# Artemis_Thing_Plus.net
KiCad netlist of a schematic drawn in EAGLE
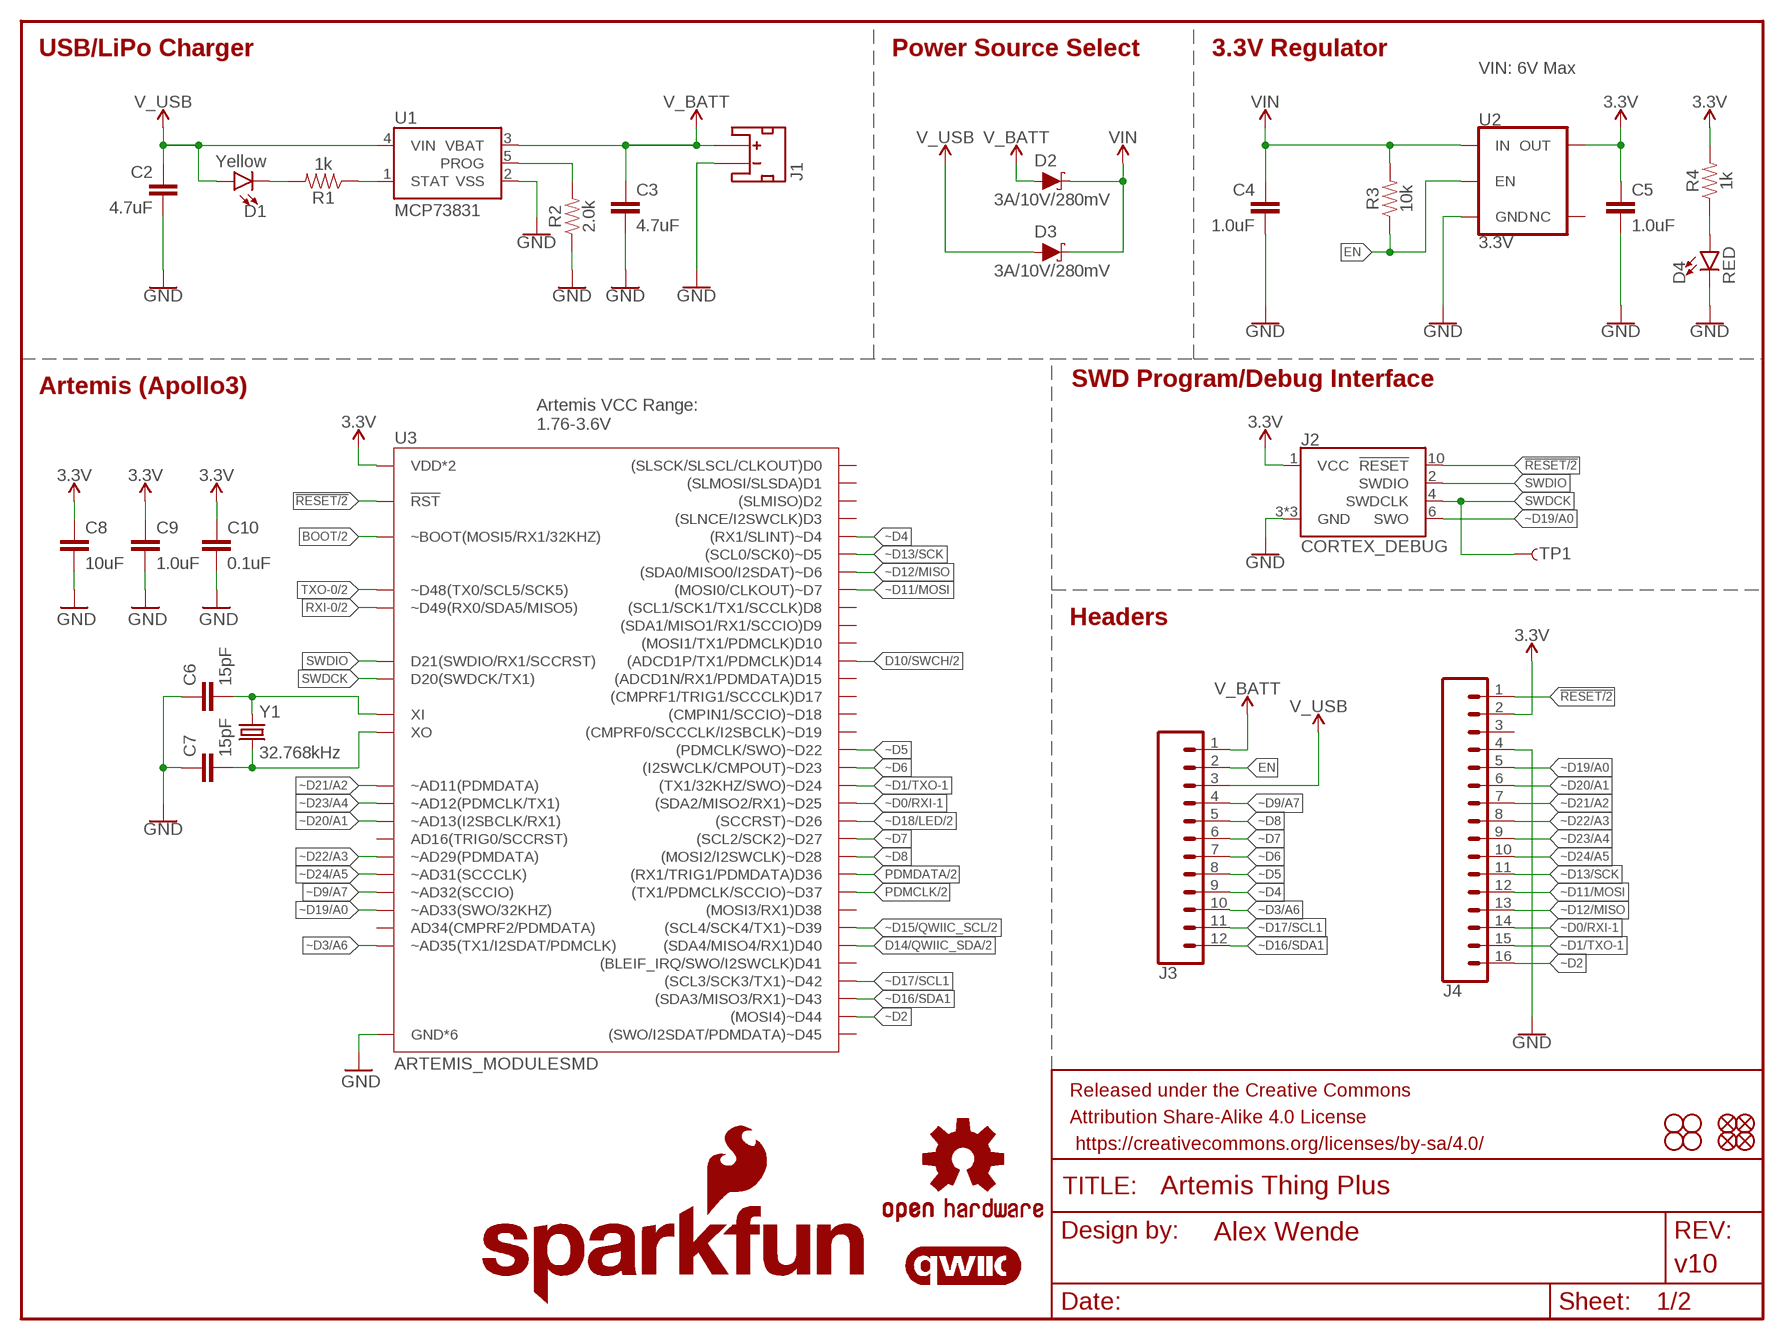
[diagram p0: schematic, sheet 1]
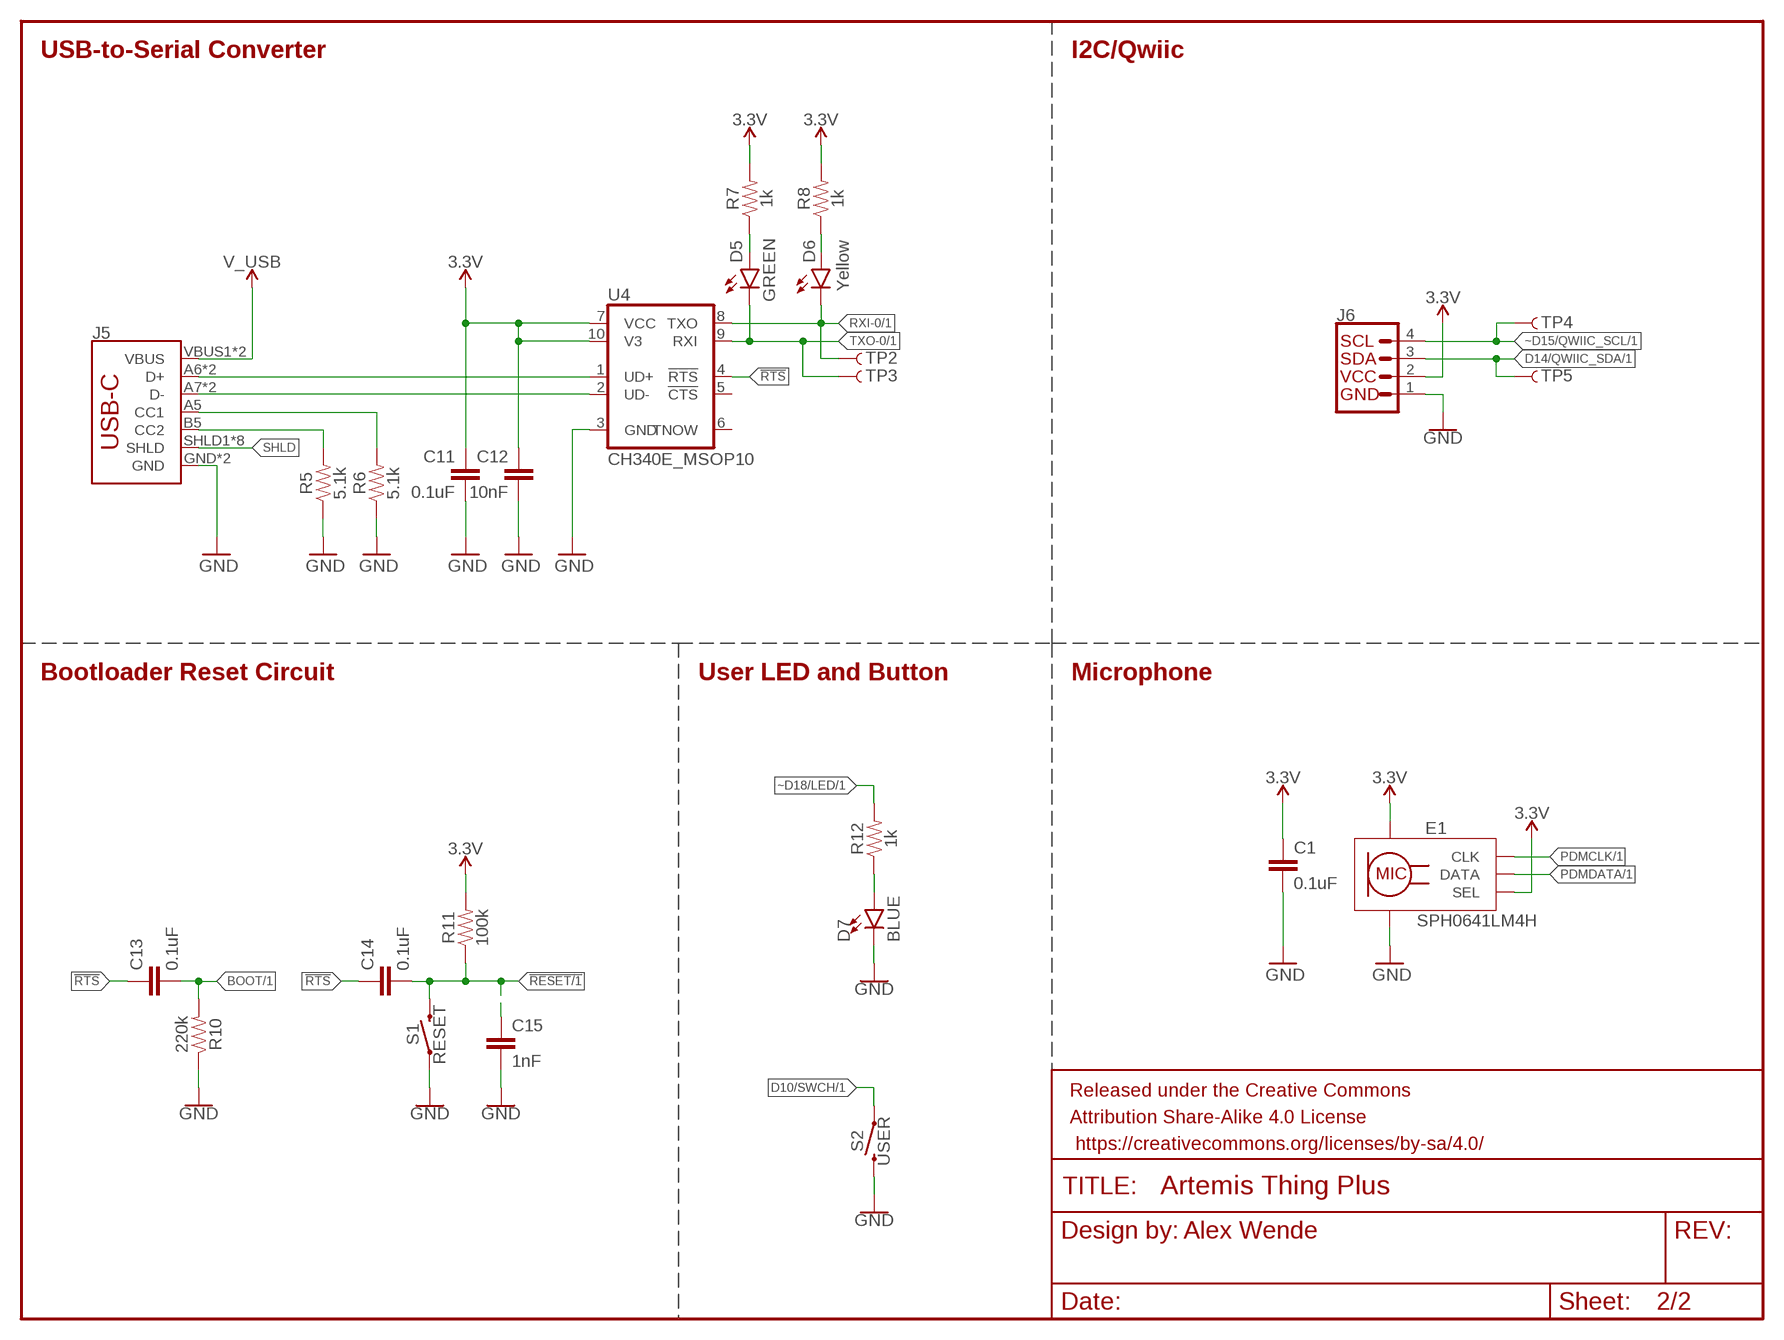
[diagram p1: schematic, sheet 2]

(export (version "E")
  (design (tool "Eeschema 10.0.6"))
  (components
    (comp (ref "C2")
      (value "4.7uF")
      (footprint "eagle-import:0603")
      (libsource (lib "eagle-import") (part "4.7UF-0603-6.3V-(10%)"))
    )
    (comp (ref "C3")
      (value "4.7uF")
      (footprint "eagle-import:0603")
      (libsource (lib "eagle-import") (part "4.7UF-0603-6.3V-(10%)"))
    )
    (comp (ref "C4")
      (value "1.0uF")
      (footprint "eagle-import:0402-TIGHT")
      (libsource (lib "eagle-import") (part "1.0UF-0402T-16V-10%"))
    )
    (comp (ref "C5")
      (value "1.0uF")
      (footprint "eagle-import:0402-TIGHT")
      (libsource (lib "eagle-import") (part "1.0UF-0402T-16V-10%"))
    )
    (comp (ref "C6")
      (value "15pF")
      (footprint "eagle-import:0603")
      (libsource (lib "eagle-import") (part "15PF-0603-50V-5%"))
    )
    (comp (ref "C7")
      (value "15pF")
      (footprint "eagle-import:0603")
      (libsource (lib "eagle-import") (part "15PF-0603-50V-5%"))
    )
    (comp (ref "C8")
      (value "10uF")
      (footprint "eagle-import:0603")
      (libsource (lib "eagle-import") (part "10UF-0603-6.3V-20%"))
    )
    (comp (ref "C9")
      (value "1.0uF")
      (footprint "eagle-import:0603")
      (libsource (lib "eagle-import") (part "1.0UF-0603-16V-10%"))
    )
    (comp (ref "C10")
      (value "0.1uF")
      (footprint "eagle-import:0603")
      (libsource (lib "eagle-import") (part "0.1UF-0603-25V-(+80/-20%)"))
    )
    (comp (ref "D1")
      (value "Yellow")
      (footprint "eagle-import:LED-0603")
      (libsource (lib "eagle-import") (part "LED-YELLOW0603"))
    )
    (comp (ref "D2")
      (value "3A/10V/280mV")
      (footprint "eagle-import:SOD-323")
      (libsource (lib "eagle-import") (part "DIODE-SCHOTTKY-BAT60A"))
    )
    (comp (ref "D3")
      (value "3A/10V/280mV")
      (footprint "eagle-import:SOD-323")
      (libsource (lib "eagle-import") (part "DIODE-SCHOTTKY-BAT60A"))
    )
    (comp (ref "D4")
      (value "RED")
      (footprint "eagle-import:LED-0603")
      (libsource (lib "eagle-import") (part "LED-RED0603"))
    )
    (comp (ref "FD1")
      (value "FIDUCIALUFIDUCIAL")
      (footprint "eagle-import:FIDUCIAL-MICRO")
      (libsource (lib "eagle-import") (part "FIDUCIALUFIDUCIAL"))
    )
    (comp (ref "FD2")
      (value "FIDUCIALUFIDUCIAL")
      (footprint "eagle-import:FIDUCIAL-MICRO")
      (libsource (lib "eagle-import") (part "FIDUCIALUFIDUCIAL"))
    )
    (comp (ref "FD3")
      (value "FIDUCIALUFIDUCIAL")
      (footprint "eagle-import:FIDUCIAL-MICRO")
      (libsource (lib "eagle-import") (part "FIDUCIALUFIDUCIAL"))
    )
    (comp (ref "FD4")
      (value "FIDUCIALUFIDUCIAL")
      (footprint "eagle-import:FIDUCIAL-MICRO")
      (libsource (lib "eagle-import") (part "FIDUCIALUFIDUCIAL"))
    )
    (comp (ref "FRAME1")
      (value "FRAME-LETTER")
      (footprint "eagle-import:CREATIVE_COMMONS")
      (fields (field (name "DESIGNER") "Alex Wende") (field (name "REV") "v10"))
      (libsource (lib "eagle-import") (part "FRAME-LETTER"))
    )
    (comp (ref "H1")
      (value "STAND-OFF")
      (footprint "eagle-import:STAND-OFF")
      (libsource (lib "eagle-import") (part "STAND-OFF"))
    )
    (comp (ref "H2")
      (value "STAND-OFF")
      (footprint "eagle-import:STAND-OFF")
      (libsource (lib "eagle-import") (part "STAND-OFF"))
    )
    (comp (ref "H3")
      (value "STAND-OFF")
      (footprint "eagle-import:STAND-OFF")
      (libsource (lib "eagle-import") (part "STAND-OFF"))
    )
    (comp (ref "H4")
      (value "STAND-OFF")
      (footprint "eagle-import:STAND-OFF")
      (libsource (lib "eagle-import") (part "STAND-OFF"))
    )
    (comp (ref "J1")
      (value "JST_2MM_MALE")
      (footprint "eagle-import:JST-2-SMD")
      (libsource (lib "eagle-import") (part "JST_2MM_MALE"))
    )
    (comp (ref "J2")
      (value "CORTEX_DEBUG")
      (footprint "eagle-import:2X5-PTH-1.27MM-NO_SILK")
      (libsource (lib "eagle-import") (part "CORTEX_DEBUG_MINIMUM_PTH_NS"))
    )
    (comp (ref "J3")
      (value "CONN_12SM_SQ_NO_SILK")
      (footprint "eagle-import:1X12_SM_SQ_NOSILK")
      (libsource (lib "eagle-import") (part "CONN_12SM_SQ_NO_SILK"))
    )
    (comp (ref "J4")
      (value "CONN_161X16_SM_SQ_NOSILK")
      (footprint "eagle-import:1X16_SM_SQ_NOSILK")
      (libsource (lib "eagle-import") (part "CONN_161X16_SM_SQ_NOSILK"))
    )
    (comp (ref "LOGO1")
      (value "OSHW-LOGOS")
      (footprint "eagle-import:OSHW-LOGO-S")
      (libsource (lib "eagle-import") (part "OSHW-LOGOS"))
    )
    (comp (ref "LOGO2")
      (value "QWIIC_LOGO_5MM")
      (footprint "eagle-import:QWIIC_5MM")
      (libsource (lib "eagle-import") (part "QWIIC_LOGO_5MM"))
    )
    (comp (ref "LOGO3")
      (value "SFE_LOGO_NAME_FLAME.1_INCH")
      (footprint "eagle-import:SFE_LOGO_NAME_FLAME_.1")
      (libsource (lib "eagle-import") (part "SFE_LOGO_NAME_FLAME.1_INCH"))
    )
    (comp (ref "R1")
      (value "1k")
      (footprint "eagle-import:0603")
      (libsource (lib "eagle-import") (part "1KOHM-0603-1/10W-1%"))
    )
    (comp (ref "R2")
      (value "2.0k")
      (footprint "eagle-import:0603")
      (libsource (lib "eagle-import") (part "2.0KOHM-0603-1/10W-5%"))
    )
    (comp (ref "R3")
      (value "10k")
      (footprint "eagle-import:0603")
      (libsource (lib "eagle-import") (part "10KOHM-0603-1/10W-1%"))
    )
    (comp (ref "R4")
      (value "1k")
      (footprint "eagle-import:0603")
      (libsource (lib "eagle-import") (part "1KOHM-0603-1/10W-1%"))
    )
    (comp (ref "TP1")
      (value "TEST-POINTTP_15TH_THRU")
      (footprint "eagle-import:TP_15TH")
      (libsource (lib "eagle-import") (part "TEST-POINTTP_15TH_THRU"))
    )
    (comp (ref "U1")
      (value "MCP73831")
      (footprint "eagle-import:SOT23-5")
      (libsource (lib "eagle-import") (part "MCP73831"))
    )
    (comp (ref "U2")
      (value "3.3V")
      (footprint "eagle-import:SOT23-5")
      (libsource (lib "eagle-import") (part "V_REG_AP2112K-3.3V"))
    )
    (comp (ref "U3")
      (value "ARTEMIS_MODULESMD")
      (footprint "eagle-import:ARTEMIS_FP")
      (libsource (lib "eagle-import") (part "ARTEMIS_MODULESMD"))
    )
    (comp (ref "Y1")
      (value "32.768kHz")
      (footprint "eagle-import:CRYSTAL-SMD-3.2X1.5MM")
      (libsource (lib "eagle-import") (part "CRYSTAL-32.768KHZSMD-3.2X1.5"))
    )
    (comp (ref "C1")
      (value "0.1uF")
      (footprint "eagle-import:0402-TIGHT")
      (libsource (lib "eagle-import") (part "0.1UF-0402T-16V-10%"))
    )
    (comp (ref "C11")
      (value "0.1uF")
      (footprint "eagle-import:0603")
      (libsource (lib "eagle-import") (part "0.1UF-0603-25V-(+80/-20%)"))
    )
    (comp (ref "C12")
      (value "10nF")
      (footprint "eagle-import:0603")
      (libsource (lib "eagle-import") (part "10NF-0603-50V-10%"))
    )
    (comp (ref "C13")
      (value "0.1uF")
      (footprint "eagle-import:0603")
      (libsource (lib "eagle-import") (part "0.1UF-0603-25V-5%"))
    )
    (comp (ref "C14")
      (value "0.1uF")
      (footprint "eagle-import:0603")
      (libsource (lib "eagle-import") (part "0.1UF-0603-25V-5%"))
    )
    (comp (ref "C15")
      (value "1nF")
      (footprint "eagle-import:0603")
      (libsource (lib "eagle-import") (part "1.0NF/1000PF-0603-50V-10%"))
    )
    (comp (ref "D5")
      (value "GREEN")
      (footprint "eagle-import:LED-0603")
      (libsource (lib "eagle-import") (part "LED-GREEN0603"))
    )
    (comp (ref "D6")
      (value "Yellow")
      (footprint "eagle-import:LED-0603")
      (libsource (lib "eagle-import") (part "LED-YELLOW0603"))
    )
    (comp (ref "D7")
      (value "BLUE")
      (footprint "eagle-import:LED-0603")
      (libsource (lib "eagle-import") (part "LED-BLUE0603"))
    )
    (comp (ref "E1")
      (value "SPH0641LM4H")
      (footprint "eagle-import:SPH0641LM4H-1_MICROPHONE")
      (libsource (lib "eagle-import") (part "SPH0641LM4H-1_MICROPHONE"))
    )
    (comp (ref "FRAME2")
      (value "FRAME-LETTERNO_PACKAGE")
      (footprint "eagle-import:DUMMY")
      (fields (field (name "DESIGNER") "Nobody"))
      (libsource (lib "eagle-import") (part "FRAME-LETTERNO_PACKAGE"))
    )
    (comp (ref "J5")
      (value "USB-C")
      (footprint "eagle-import:USB-C-16P")
      (libsource (lib "eagle-import") (part "USB_C2-LAYER"))
    )
    (comp (ref "J6")
      (value "QWIIC_CONNECTORJS-1MM")
      (footprint "eagle-import:JST04_1MM_RA")
      (libsource (lib "eagle-import") (part "QWIIC_CONNECTORJS-1MM"))
    )
    (comp (ref "R5")
      (value "5.1k")
      (footprint "eagle-import:0603")
      (libsource (lib "eagle-import") (part "5.1KOHM5.1KOHM-0603-1/10W-1%"))
    )
    (comp (ref "R6")
      (value "5.1k")
      (footprint "eagle-import:0603")
      (libsource (lib "eagle-import") (part "5.1KOHM5.1KOHM-0603-1/10W-1%"))
    )
    (comp (ref "R7")
      (value "1k")
      (footprint "eagle-import:0603")
      (libsource (lib "eagle-import") (part "1KOHM-0603-1/10W-1%"))
    )
    (comp (ref "R8")
      (value "1k")
      (footprint "eagle-import:0603")
      (libsource (lib "eagle-import") (part "1KOHM-0603-1/10W-1%"))
    )
    (comp (ref "R10")
      (value "220k")
      (footprint "eagle-import:0603")
      (libsource (lib "eagle-import") (part "220KOHM-0603-1/10W-1%"))
    )
    (comp (ref "R11")
      (value "100k")
      (footprint "eagle-import:0603")
      (libsource (lib "eagle-import") (part "100KOHM-0603-1/10W-1%"))
    )
    (comp (ref "R12")
      (value "1k")
      (footprint "eagle-import:0603")
      (libsource (lib "eagle-import") (part "1KOHM-0603-1/10W-1%"))
    )
    (comp (ref "S1")
      (value "RESET")
      (footprint "eagle-import:TACTILE_SWITCH_SMD_4.6X2.8MM")
      (libsource (lib "eagle-import") (part "MOMENTARY-SWITCH-SPST-SMD-4.6X2.8MM"))
    )
    (comp (ref "S2")
      (value "USER")
      (footprint "eagle-import:TACTILE_SWITCH_SMD_4.6X2.8MM")
      (libsource (lib "eagle-import") (part "MOMENTARY-SWITCH-SPST-SMD-4.6X2.8MM"))
    )
    (comp (ref "TP2")
      (value "TEST-POINTTP_15TH_THRU")
      (footprint "eagle-import:TP_15TH")
      (libsource (lib "eagle-import") (part "TEST-POINTTP_15TH_THRU"))
    )
    (comp (ref "TP3")
      (value "TEST-POINTTP_15TH_THRU")
      (footprint "eagle-import:TP_15TH")
      (libsource (lib "eagle-import") (part "TEST-POINTTP_15TH_THRU"))
    )
    (comp (ref "TP4")
      (value "TEST-POINTTP_15TH_THRU")
      (footprint "eagle-import:TP_15TH")
      (libsource (lib "eagle-import") (part "TEST-POINTTP_15TH_THRU"))
    )
    (comp (ref "TP5")
      (value "TEST-POINTTP_15TH_THRU")
      (footprint "eagle-import:TP_15TH")
      (libsource (lib "eagle-import") (part "TEST-POINTTP_15TH_THRU"))
    )
    (comp (ref "U4")
      (value "CH340E_MSOP10")
      (footprint "eagle-import:MSOP10")
      (libsource (lib "eagle-import") (part "CH340E_MSOP10"))
    )
  )
  (nets
    (net (code "1") (name "3.3V") (class "Default")
      (node (ref "C1") (pin "1") (pinfunction "1_1") (pintype "passive"))
      (node (ref "C10") (pin "1") (pinfunction "1_1") (pintype "passive"))
      (node (ref "C11") (pin "1") (pinfunction "1_1") (pintype "passive"))
      (node (ref "C12") (pin "1") (pinfunction "1_1") (pintype "passive"))
      (node (ref "C5") (pin "1") (pinfunction "1_1") (pintype "passive"))
      (node (ref "C8") (pin "1") (pinfunction "1_1") (pintype "passive"))
      (node (ref "C9") (pin "1") (pinfunction "1_1") (pintype "passive"))
      (node (ref "E1") (pin "2") (pinfunction "SEL_2") (pintype "input"))
      (node (ref "E1") (pin "5") (pinfunction "VDD_5") (pintype "power_in"))
      (node (ref "J2") (pin "1") (pinfunction "VCC_1") (pintype "bidirectional"))
      (node (ref "J4") (pin "2") (pinfunction "2_2") (pintype "passive"))
      (node (ref "J6") (pin "2") (pinfunction "2_2") (pintype "power_in"))
      (node (ref "R11") (pin "2") (pinfunction "2_2") (pintype "passive"))
      (node (ref "R4") (pin "2") (pinfunction "2_2") (pintype "passive"))
      (node (ref "R7") (pin "2") (pinfunction "2_2") (pintype "passive"))
      (node (ref "R8") (pin "2") (pinfunction "2_2") (pintype "passive"))
      (node (ref "U2") (pin "5") (pinfunction "OUT_5") (pintype "passive"))
      (node (ref "U3") (pin "VDD@36") (pinfunction "VDD*2_VDD@36") (pintype "bidirectional"))
      (node (ref "U3") (pin "VDD@37") (pinfunction "VDD*2_VDD@37") (pintype "bidirectional"))
      (node (ref "U4") (pin "10") (pinfunction "V3_10") (pintype "bidirectional"))
      (node (ref "U4") (pin "7") (pinfunction "VCC_7") (pintype "bidirectional"))
    )
    (net (code "2") (name "BOOT") (class "Default")
      (node (ref "C13") (pin "2") (pinfunction "2_2") (pintype "passive"))
      (node (ref "R10") (pin "2") (pinfunction "2_2") (pintype "passive"))
      (node (ref "U3") (pin "BOOT") (pinfunction "~{BOOT(MOSI5/RX1/32KHZ})_BOOT") (pintype "bidirectional"))
    )
    (net (code "3") (name "D10{slash}SWCH") (class "Default")
      (node (ref "S2") (pin "1") (pinfunction "1_1") (pintype "passive"))
      (node (ref "S2") (pin "2") (pinfunction "1_2") (pintype "passive"))
      (node (ref "U3") (pin "D14") (pinfunction "(ADCD1P/TX1/PDMCLK)D14_D14") (pintype "bidirectional"))
    )
    (net (code "4") (name "D14{slash}QWIIC_SDA") (class "Default")
      (node (ref "J6") (pin "3") (pinfunction "3_3") (pintype "passive"))
      (node (ref "TP5") (pin "P$1") (pinfunction "1_P$1") (pintype "bidirectional"))
      (node (ref "U3") (pin "D40") (pinfunction "(SDA4/MISO4/RX1)D40_D40") (pintype "bidirectional"))
    )
    (net (code "5") (name "EN") (class "Default")
      (node (ref "J3") (pin "2") (pinfunction "2_2") (pintype "passive"))
      (node (ref "R3") (pin "1") (pinfunction "1_1") (pintype "passive"))
      (node (ref "U2") (pin "3") (pinfunction "EN_3") (pintype "input"))
    )
    (net (code "6") (name "GND") (class "Default")
      (node (ref "C1") (pin "2") (pinfunction "2_2") (pintype "passive"))
      (node (ref "C10") (pin "2") (pinfunction "2_2") (pintype "passive"))
      (node (ref "C11") (pin "2") (pinfunction "2_2") (pintype "passive"))
      (node (ref "C12") (pin "2") (pinfunction "2_2") (pintype "passive"))
      (node (ref "C15") (pin "2") (pinfunction "2_2") (pintype "passive"))
      (node (ref "C2") (pin "2") (pinfunction "2_2") (pintype "passive"))
      (node (ref "C3") (pin "2") (pinfunction "2_2") (pintype "passive"))
      (node (ref "C4") (pin "2") (pinfunction "2_2") (pintype "passive"))
      (node (ref "C5") (pin "2") (pinfunction "2_2") (pintype "passive"))
      (node (ref "C6") (pin "1") (pinfunction "1_1") (pintype "passive"))
      (node (ref "C7") (pin "1") (pinfunction "1_1") (pintype "passive"))
      (node (ref "C8") (pin "2") (pinfunction "2_2") (pintype "passive"))
      (node (ref "C9") (pin "2") (pinfunction "2_2") (pintype "passive"))
      (node (ref "D4") (pin "C") (pinfunction "C_C") (pintype "passive"))
      (node (ref "D7") (pin "C") (pinfunction "C_C") (pintype "passive"))
      (node (ref "E1") (pin "3") (pinfunction "GND_3") (pintype "power_in"))
      (node (ref "E1") (pin "6") (pinfunction "GND_6") (pintype "power_in"))
      (node (ref "E1") (pin "7") (pinfunction "GND_7") (pintype "power_in"))
      (node (ref "E1") (pin "8") (pinfunction "GND_8") (pintype "power_in"))
      (node (ref "J1") (pin "1") (pinfunction "-_1") (pintype "bidirectional"))
      (node (ref "J2") (pin "3") (pinfunction "GND_3") (pintype "bidirectional"))
      (node (ref "J2") (pin "5") (pinfunction "GND_5") (pintype "bidirectional"))
      (node (ref "J2") (pin "9") (pinfunction "GND_9") (pintype "bidirectional"))
      (node (ref "J4") (pin "4") (pinfunction "4_4") (pintype "passive"))
      (node (ref "J5") (pin "GND") (pinfunction "GND_GND") (pintype "bidirectional"))
      (node (ref "J5") (pin "GND2") (pinfunction "GND_GND2") (pintype "bidirectional"))
      (node (ref "J6") (pin "1") (pinfunction "1_1") (pintype "power_in"))
      (node (ref "R10") (pin "1") (pinfunction "1_1") (pintype "passive"))
      (node (ref "R2") (pin "1") (pinfunction "1_1") (pintype "passive"))
      (node (ref "R5") (pin "1") (pinfunction "1_1") (pintype "passive"))
      (node (ref "R6") (pin "1") (pinfunction "1_1") (pintype "passive"))
      (node (ref "S1") (pin "1") (pinfunction "1_1") (pintype "passive"))
      (node (ref "S1") (pin "2") (pinfunction "1_2") (pintype "passive"))
      (node (ref "S2") (pin "3") (pinfunction "2_3") (pintype "passive"))
      (node (ref "S2") (pin "4") (pinfunction "2_4") (pintype "passive"))
      (node (ref "U1") (pin "2") (pinfunction "VSS_2") (pintype "power_in"))
      (node (ref "U2") (pin "2") (pinfunction "GND_2") (pintype "input"))
      (node (ref "U3") (pin "GND@1") (pinfunction "GND*6_GND@1") (pintype "bidirectional"))
      (node (ref "U3") (pin "GND@22") (pinfunction "GND*6_GND@22") (pintype "bidirectional"))
      (node (ref "U3") (pin "GND@38") (pinfunction "GND*6_GND@38") (pintype "bidirectional"))
      (node (ref "U3") (pin "GND@39") (pinfunction "GND*6_GND@39") (pintype "bidirectional"))
      (node (ref "U3") (pin "GND@47") (pinfunction "GND*6_GND@47") (pintype "bidirectional"))
      (node (ref "U3") (pin "GND@59") (pinfunction "GND*6_GND@59") (pintype "bidirectional"))
      (node (ref "U4") (pin "3") (pinfunction "GND_3") (pintype "bidirectional"))
    )
    (net (code "7") (name "Net-(D1-PadC)") (class "Default")
      (node (ref "D1") (pin "C") (pinfunction "C_C") (pintype "passive"))
      (node (ref "R1") (pin "2") (pinfunction "2_2") (pintype "passive"))
    )
    (net (code "8") (name "Net-(D4-PadA)") (class "Default")
      (node (ref "D4") (pin "A") (pinfunction "A_A") (pintype "passive"))
      (node (ref "R4") (pin "1") (pinfunction "1_1") (pintype "passive"))
    )
    (net (code "9") (name "Net-(D5-PadA)") (class "Default")
      (node (ref "D5") (pin "A") (pinfunction "A_A") (pintype "passive"))
      (node (ref "R7") (pin "1") (pinfunction "1_1") (pintype "passive"))
    )
    (net (code "10") (name "Net-(D6-PadA)") (class "Default")
      (node (ref "D6") (pin "A") (pinfunction "A_A") (pintype "passive"))
      (node (ref "R8") (pin "1") (pinfunction "1_1") (pintype "passive"))
    )
    (net (code "11") (name "Net-(D7-PadA)") (class "Default")
      (node (ref "D7") (pin "A") (pinfunction "A_A") (pintype "passive"))
      (node (ref "R12") (pin "1") (pinfunction "1_1") (pintype "passive"))
    )
    (net (code "12") (name "Net-(J5-CC1)") (class "Default")
      (node (ref "J5") (pin "A5") (pinfunction "CC1_A5") (pintype "bidirectional"))
      (node (ref "R6") (pin "2") (pinfunction "2_2") (pintype "passive"))
    )
    (net (code "13") (name "Net-(J5-CC2)") (class "Default")
      (node (ref "J5") (pin "B5") (pinfunction "CC2_B5") (pintype "bidirectional"))
      (node (ref "R5") (pin "2") (pinfunction "2_2") (pintype "passive"))
    )
    (net (code "14") (name "Net-(U1-PROG)") (class "Default")
      (node (ref "R2") (pin "2") (pinfunction "2_2") (pintype "passive"))
      (node (ref "U1") (pin "5") (pinfunction "PROG_5") (pintype "input"))
    )
    (net (code "15") (name "Net-(U1-STAT)") (class "Default")
      (node (ref "R1") (pin "1") (pinfunction "1_1") (pintype "passive"))
      (node (ref "U1") (pin "1") (pinfunction "STAT_1") (pintype "output"))
    )
    (net (code "16") (name "Net-(U4-UD+)") (class "Default")
      (node (ref "J5") (pin "A6") (pinfunction "D+_A6") (pintype "bidirectional"))
      (node (ref "J5") (pin "B6") (pinfunction "D+_B6") (pintype "bidirectional"))
      (node (ref "U4") (pin "1") (pinfunction "UD+_1") (pintype "bidirectional"))
    )
    (net (code "17") (name "Net-(U4-UD-)") (class "Default")
      (node (ref "J5") (pin "A7") (pinfunction "D-_A7") (pintype "bidirectional"))
      (node (ref "J5") (pin "B7") (pinfunction "D-_B7") (pintype "bidirectional"))
      (node (ref "U4") (pin "2") (pinfunction "UD-_2") (pintype "bidirectional"))
    )
    (net (code "18") (name "Net-(Y1-1)") (class "Default")
      (node (ref "C6") (pin "2") (pinfunction "2_2") (pintype "passive"))
      (node (ref "U3") (pin "XI") (pinfunction "XI_XI") (pintype "bidirectional"))
      (node (ref "Y1") (pin "P$1") (pinfunction "1_P$1") (pintype "passive"))
    )
    (net (code "19") (name "Net-(Y1-2)") (class "Default")
      (node (ref "C7") (pin "2") (pinfunction "2_2") (pintype "passive"))
      (node (ref "U3") (pin "XO") (pinfunction "XO_XO") (pintype "bidirectional"))
      (node (ref "Y1") (pin "P$2") (pinfunction "2_P$2") (pintype "passive"))
    )
    (net (code "20") (name "PDMCLK") (class "Default")
      (node (ref "E1") (pin "4") (pinfunction "CLK_4") (pintype "input"))
      (node (ref "U3") (pin "~D37") (pinfunction "(TX1/PDMCLK/SCCIO)~{D37}_~D37") (pintype "bidirectional"))
    )
    (net (code "21") (name "PDMDATA") (class "Default")
      (node (ref "E1") (pin "1") (pinfunction "DATA_1") (pintype "output"))
      (node (ref "U3") (pin "D36") (pinfunction "(RX1/TRIG1/PDMDATA)D36_D36") (pintype "bidirectional"))
    )
    (net (code "22") (name "RXI-0") (class "Default")
      (node (ref "D6") (pin "C") (pinfunction "C_C") (pintype "passive"))
      (node (ref "TP2") (pin "P$1") (pinfunction "1_P$1") (pintype "bidirectional"))
      (node (ref "U3") (pin "RXI-0") (pinfunction "~{D49(RX0/SDA5/MISO5})_RXI-0") (pintype "bidirectional"))
      (node (ref "U4") (pin "8") (pinfunction "TXO_8") (pintype "bidirectional"))
    )
    (net (code "23") (name "SHLD") (class "Default")
      (node (ref "J5") (pin "SHLD1") (pinfunction "SHLD_SHLD1") (pintype "bidirectional"))
      (node (ref "J5") (pin "SHLD2") (pinfunction "SHLD_SHLD2") (pintype "bidirectional"))
      (node (ref "J5") (pin "SHLD3") (pinfunction "SHLD_SHLD3") (pintype "bidirectional"))
      (node (ref "J5") (pin "SHLD4") (pinfunction "SHLD_SHLD4") (pintype "bidirectional"))
      (node (ref "J5") (pin "SHLD5") (pinfunction "SHLD_SHLD5") (pintype "bidirectional"))
      (node (ref "J5") (pin "SHLD6") (pinfunction "SHLD_SHLD6") (pintype "bidirectional"))
      (node (ref "J5") (pin "SHLD7") (pinfunction "SHLD_SHLD7") (pintype "bidirectional"))
      (node (ref "J5") (pin "SHLD8") (pinfunction "SHLD_SHLD8") (pintype "bidirectional"))
    )
    (net (code "24") (name "SWDCK") (class "Default")
      (node (ref "J2") (pin "4") (pinfunction "SWDCLK_4") (pintype "bidirectional"))
      (node (ref "TP1") (pin "P$1") (pinfunction "1_P$1") (pintype "bidirectional"))
      (node (ref "U3") (pin "SWDCK") (pinfunction "D20(SWDCK/TX1)_SWDCK") (pintype "bidirectional"))
    )
    (net (code "25") (name "SWDIO") (class "Default")
      (node (ref "J2") (pin "2") (pinfunction "SWDIO_2") (pintype "bidirectional"))
      (node (ref "U3") (pin "SWDIO") (pinfunction "D21(SWDIO/RX1/SCCRST)_SWDIO") (pintype "bidirectional"))
    )
    (net (code "26") (name "TXO-0") (class "Default")
      (node (ref "D5") (pin "C") (pinfunction "C_C") (pintype "passive"))
      (node (ref "TP3") (pin "P$1") (pinfunction "1_P$1") (pintype "bidirectional"))
      (node (ref "U3") (pin "TXO-0") (pinfunction "~{D48(TX0/SCL5/SCK5})_TXO-0") (pintype "bidirectional"))
      (node (ref "U4") (pin "9") (pinfunction "RXI_9") (pintype "bidirectional"))
    )
    (net (code "27") (name "VIN") (class "Default")
      (node (ref "C4") (pin "1") (pinfunction "1_1") (pintype "passive"))
      (node (ref "D2") (pin "C") (pinfunction "C_C") (pintype "passive"))
      (node (ref "D3") (pin "C") (pinfunction "C_C") (pintype "passive"))
      (node (ref "R3") (pin "2") (pinfunction "2_2") (pintype "passive"))
      (node (ref "U2") (pin "1") (pinfunction "IN_1") (pintype "input"))
    )
    (net (code "28") (name "V_BATT") (class "Default")
      (node (ref "C3") (pin "1") (pinfunction "1_1") (pintype "passive"))
      (node (ref "D2") (pin "A") (pinfunction "A_A") (pintype "passive"))
      (node (ref "J1") (pin "2") (pinfunction "+_2") (pintype "bidirectional"))
      (node (ref "J3") (pin "1") (pinfunction "1_1") (pintype "passive"))
      (node (ref "U1") (pin "3") (pinfunction "VBAT_3") (pintype "power_in"))
    )
    (net (code "29") (name "V_USB") (class "Default")
      (node (ref "C2") (pin "1") (pinfunction "1_1") (pintype "passive"))
      (node (ref "D1") (pin "A") (pinfunction "A_A") (pintype "passive"))
      (node (ref "D3") (pin "A") (pinfunction "A_A") (pintype "passive"))
      (node (ref "J3") (pin "3") (pinfunction "3_3") (pintype "passive"))
      (node (ref "J5") (pin "VBUS1") (pinfunction "VBUS_VBUS1") (pintype "bidirectional"))
      (node (ref "J5") (pin "VBUS2") (pinfunction "VBUS_VBUS2") (pintype "bidirectional"))
      (node (ref "U1") (pin "4") (pinfunction "VIN_4") (pintype "power_in"))
    )
    (net (code "30") (name "unconnected-(J1-PAD1-PadNC1)") (class "Default")
      (node (ref "J1") (pin "NC1") (pinfunction "PAD1_NC1") (pintype "bidirectional"))
    )
    (net (code "31") (name "unconnected-(J1-PAD2-PadNC2)") (class "Default")
      (node (ref "J1") (pin "NC2") (pinfunction "PAD2_NC2") (pintype "bidirectional"))
    )
    (net (code "32") (name "unconnected-(J4-Pad3)") (class "Default")
      (node (ref "J4") (pin "3") (pinfunction "3_3") (pintype "passive"))
    )
    (net (code "33") (name "unconnected-(U2-NC-Pad4)") (class "Default")
      (node (ref "U2") (pin "4") (pinfunction "NC_4") (pintype "no_connect"))
    )
    (net (code "34") (name "unconnected-(U3-(ADCD1N{slash}RX1{slash}PDMDATA)D15-PadD15)") (class "Default")
      (node (ref "U3") (pin "D15") (pinfunction "(ADCD1N/RX1/PDMDATA)D15_D15") (pintype "bidirectional"))
    )
    (net (code "35") (name "unconnected-(U3-(BLEIF_IRQ{slash}SWO{slash}I2SWCLK)D41-PadD41)") (class "Default")
      (node (ref "U3") (pin "D41") (pinfunction "(BLEIF_IRQ/SWO/I2SWCLK)D41_D41") (pintype "bidirectional"))
    )
    (net (code "36") (name "unconnected-(U3-(CMPIN1{slash}SCCIO)~{D18}-Pad~D18)") (class "Default")
      (node (ref "U3") (pin "~D18") (pinfunction "(CMPIN1/SCCIO)~{D18}_~D18") (pintype "bidirectional"))
    )
    (net (code "37") (name "unconnected-(U3-(CMPRF0{slash}SCCCLK{slash}I2SBCLK)~{D19}-Pad~D19)") (class "Default")
      (node (ref "U3") (pin "~D19") (pinfunction "(CMPRF0/SCCCLK/I2SBCLK)~{D19}_~D19") (pintype "bidirectional"))
    )
    (net (code "38") (name "unconnected-(U3-(CMPRF1{slash}TRIG1{slash}SCCCLK)D17-PadD17)") (class "Default")
      (node (ref "U3") (pin "D17") (pinfunction "(CMPRF1/TRIG1/SCCCLK)D17_D17") (pintype "bidirectional"))
    )
    (net (code "39") (name "unconnected-(U3-(MOSI1{slash}TX1{slash}PDMCLK)D10-PadD10)") (class "Default")
      (node (ref "U3") (pin "D10") (pinfunction "(MOSI1/TX1/PDMCLK)D10_D10") (pintype "bidirectional"))
    )
    (net (code "40") (name "unconnected-(U3-(MOSI3{slash}RX1)D38-PadD38)") (class "Default")
      (node (ref "U3") (pin "D38") (pinfunction "(MOSI3/RX1)D38_D38") (pintype "bidirectional"))
    )
    (net (code "41") (name "unconnected-(U3-(SCL1{slash}SCK1{slash}TX1{slash}SCCLK)D8-PadD8)") (class "Default")
      (node (ref "U3") (pin "D8") (pinfunction "(SCL1/SCK1/TX1/SCCLK)D8_D8") (pintype "bidirectional"))
    )
    (net (code "42") (name "unconnected-(U3-(SDA1{slash}MISO1{slash}RX1{slash}SCCIO)D9-PadD9)") (class "Default")
      (node (ref "U3") (pin "D9") (pinfunction "(SDA1/MISO1/RX1/SCCIO)D9_D9") (pintype "bidirectional"))
    )
    (net (code "43") (name "unconnected-(U3-(SLMISO)D2-PadD2)") (class "Default")
      (node (ref "U3") (pin "D2") (pinfunction "(SLMISO)D2_D2") (pintype "bidirectional"))
    )
    (net (code "44") (name "unconnected-(U3-(SLMOSI{slash}SLSDA)D1-PadD1)") (class "Default")
      (node (ref "U3") (pin "D1") (pinfunction "(SLMOSI/SLSDA)D1_D1") (pintype "bidirectional"))
    )
    (net (code "45") (name "unconnected-(U3-(SLNCE{slash}I2SWCLK)D3-PadD3)") (class "Default")
      (node (ref "U3") (pin "D3") (pinfunction "(SLNCE/I2SWCLK)D3_D3") (pintype "bidirectional"))
    )
    (net (code "46") (name "unconnected-(U3-(SLSCK{slash}SLSCL{slash}CLKOUT)D0-PadD0)") (class "Default")
      (node (ref "U3") (pin "D0") (pinfunction "(SLSCK/SLSCL/CLKOUT)D0_D0") (pintype "bidirectional"))
    )
    (net (code "47") (name "unconnected-(U3-(SWO{slash}I2SDAT{slash}PDMDATA)~{D45}-Pad~D45)") (class "Default")
      (node (ref "U3") (pin "~D45") (pinfunction "(SWO/I2SDAT/PDMDATA)~{D45}_~D45") (pintype "bidirectional"))
    )
    (net (code "48") (name "unconnected-(U3-AD16(TRIG0{slash}SCCRST)-PadAD16)") (class "Default")
      (node (ref "U3") (pin "AD16") (pinfunction "AD16(TRIG0/SCCRST)_AD16") (pintype "bidirectional"))
    )
    (net (code "49") (name "unconnected-(U3-AD34(CMPRF2{slash}PDMDATA)-PadAD34)") (class "Default")
      (node (ref "U3") (pin "AD34") (pinfunction "AD34(CMPRF2/PDMDATA)_AD34") (pintype "bidirectional"))
    )
    (net (code "50") (name "unconnected-(U4-TNOW-Pad6)") (class "Default")
      (node (ref "U4") (pin "6") (pinfunction "TNOW_6") (pintype "bidirectional"))
    )
    (net (code "51") (name "unconnected-(U4-~{CTS}-Pad5)") (class "Default")
      (node (ref "U4") (pin "5") (pinfunction "~{CTS}_5") (pintype "bidirectional"))
    )
    (net (code "52") (name "~{D0{slash}RXI-1}") (class "Default")
      (node (ref "J4") (pin "14") (pinfunction "14_14") (pintype "passive"))
      (node (ref "U3") (pin "~D25") (pinfunction "(SDA2/MISO2/RX1)~{D25}_~D25") (pintype "bidirectional"))
    )
    (net (code "53") (name "~{D1{slash}TXO-1}") (class "Default")
      (node (ref "J4") (pin "15") (pinfunction "15_15") (pintype "passive"))
      (node (ref "U3") (pin "~D24") (pinfunction "(TX1/32KHZ/SWO)~{D24}_~D24") (pintype "bidirectional"))
    )
    (net (code "54") (name "~{D2}") (class "Default")
      (node (ref "J4") (pin "16") (pinfunction "16_16") (pintype "passive"))
      (node (ref "U3") (pin "~D44") (pinfunction "(MOSI4)~{D44}_~D44") (pintype "bidirectional"))
    )
    (net (code "55") (name "~{D3{slash}A6}") (class "Default")
      (node (ref "J3") (pin "10") (pinfunction "10_10") (pintype "passive"))
      (node (ref "U3") (pin "~AD35") (pinfunction "~{AD35(TX1/I2SDAT/PDMCLK})_~AD35") (pintype "bidirectional"))
    )
    (net (code "56") (name "~{D4}") (class "Default")
      (node (ref "J3") (pin "9") (pinfunction "9_9") (pintype "passive"))
      (node (ref "U3") (pin "~D4") (pinfunction "(RX1/SLINT)~{D4}_~D4") (pintype "bidirectional"))
    )
    (net (code "57") (name "~{D5}") (class "Default")
      (node (ref "J3") (pin "8") (pinfunction "8_8") (pintype "passive"))
      (node (ref "U3") (pin "~D22") (pinfunction "(PDMCLK/SWO)~{D22}_~D22") (pintype "bidirectional"))
    )
    (net (code "58") (name "~{D6}") (class "Default")
      (node (ref "J3") (pin "7") (pinfunction "7_7") (pintype "passive"))
      (node (ref "U3") (pin "~D23") (pinfunction "(I2SWCLK/CMPOUT)~{D23}_~D23") (pintype "bidirectional"))
    )
    (net (code "59") (name "~{D7}") (class "Default")
      (node (ref "J3") (pin "6") (pinfunction "6_6") (pintype "passive"))
      (node (ref "U3") (pin "~D27") (pinfunction "(SCL2/SCK2)~{D27}_~D27") (pintype "bidirectional"))
    )
    (net (code "60") (name "~{D8}") (class "Default")
      (node (ref "J3") (pin "5") (pinfunction "5_5") (pintype "passive"))
      (node (ref "U3") (pin "~D28") (pinfunction "(MOSI2/I2SWCLK)~{D28}_~D28") (pintype "bidirectional"))
    )
    (net (code "61") (name "~{D9{slash}A7}") (class "Default")
      (node (ref "J3") (pin "4") (pinfunction "4_4") (pintype "passive"))
      (node (ref "U3") (pin "~AD32") (pinfunction "~{AD32(SCCIO})_~AD32") (pintype "bidirectional"))
    )
    (net (code "62") (name "~{D11{slash}MOSI}") (class "Default")
      (node (ref "J4") (pin "12") (pinfunction "12_12") (pintype "passive"))
      (node (ref "U3") (pin "D7") (pinfunction "(MOSI0/CLKOUT)~{D7}_D7") (pintype "bidirectional"))
    )
    (net (code "63") (name "~{D12{slash}MISO}") (class "Default")
      (node (ref "J4") (pin "13") (pinfunction "13_13") (pintype "passive"))
      (node (ref "U3") (pin "~D6") (pinfunction "(SDA0/MISO0/I2SDAT)~{D6}_~D6") (pintype "bidirectional"))
    )
    (net (code "64") (name "~{D13{slash}SCK}") (class "Default")
      (node (ref "J4") (pin "11") (pinfunction "11_11") (pintype "passive"))
      (node (ref "U3") (pin "~D5") (pinfunction "(SCL0/SCK0)~{D5}_~D5") (pintype "bidirectional"))
    )
    (net (code "65") (name "~{D15{slash}QWIIC_SCL}") (class "Default")
      (node (ref "J6") (pin "4") (pinfunction "4_4") (pintype "passive"))
      (node (ref "TP4") (pin "P$1") (pinfunction "1_P$1") (pintype "bidirectional"))
      (node (ref "U3") (pin "~D39") (pinfunction "(SCL4/SCK4/TX1)~{D39}_~D39") (pintype "bidirectional"))
    )
    (net (code "66") (name "~{D16{slash}SDA1}") (class "Default")
      (node (ref "J3") (pin "12") (pinfunction "12_12") (pintype "passive"))
      (node (ref "U3") (pin "~D43") (pinfunction "(SDA3/MISO3/RX1)~{D43}_~D43") (pintype "bidirectional"))
    )
    (net (code "67") (name "~{D17{slash}SCL1}") (class "Default")
      (node (ref "J3") (pin "11") (pinfunction "11_11") (pintype "passive"))
      (node (ref "U3") (pin "~D42") (pinfunction "(SCL3/SCK3/TX1)~{D42}_~D42") (pintype "bidirectional"))
    )
    (net (code "68") (name "~{D18{slash}LED}") (class "Default")
      (node (ref "R12") (pin "2") (pinfunction "2_2") (pintype "passive"))
      (node (ref "U3") (pin "~D26") (pinfunction "(SCCRST)~{D26}_~D26") (pintype "bidirectional"))
    )
    (net (code "69") (name "~{D19{slash}A0}") (class "Default")
      (node (ref "J2") (pin "6") (pinfunction "SWO_6") (pintype "bidirectional"))
      (node (ref "J4") (pin "5") (pinfunction "5_5") (pintype "passive"))
      (node (ref "U3") (pin "~AD33/SWO") (pinfunction "~{AD33(SWO/32KHZ})_~AD33/SWO") (pintype "bidirectional"))
    )
    (net (code "70") (name "~{D20{slash}A1}") (class "Default")
      (node (ref "J4") (pin "6") (pinfunction "6_6") (pintype "passive"))
      (node (ref "U3") (pin "~AD13") (pinfunction "~{AD13(I2SBCLK/RX1})_~AD13") (pintype "bidirectional"))
    )
    (net (code "71") (name "~{D21{slash}A2}") (class "Default")
      (node (ref "J4") (pin "7") (pinfunction "7_7") (pintype "passive"))
      (node (ref "U3") (pin "~AD11") (pinfunction "~{AD11(PDMDATA})_~AD11") (pintype "bidirectional"))
    )
    (net (code "72") (name "~{D22{slash}A3}") (class "Default")
      (node (ref "J4") (pin "8") (pinfunction "8_8") (pintype "passive"))
      (node (ref "U3") (pin "~AD29") (pinfunction "~{AD29(PDMDATA})_~AD29") (pintype "bidirectional"))
    )
    (net (code "73") (name "~{D23{slash}A4}") (class "Default")
      (node (ref "J4") (pin "9") (pinfunction "9_9") (pintype "passive"))
      (node (ref "U3") (pin "~AD12") (pinfunction "~{AD12(PDMCLK/TX1})_~AD12") (pintype "bidirectional"))
    )
    (net (code "74") (name "~{D24{slash}A5}") (class "Default")
      (node (ref "J4") (pin "10") (pinfunction "10_10") (pintype "passive"))
      (node (ref "U3") (pin "~AD31") (pinfunction "~{AD31(SCCCLK})_~AD31") (pintype "bidirectional"))
    )
    (net (code "75") (name "~{RESET}") (class "Default")
      (node (ref "C14") (pin "2") (pinfunction "2_2") (pintype "passive"))
      (node (ref "C15") (pin "1") (pinfunction "1_1") (pintype "passive"))
      (node (ref "J2") (pin "10") (pinfunction "~{RESET}_10") (pintype "bidirectional"))
      (node (ref "J4") (pin "1") (pinfunction "1_1") (pintype "passive"))
      (node (ref "R11") (pin "1") (pinfunction "1_1") (pintype "passive"))
      (node (ref "S1") (pin "3") (pinfunction "2_3") (pintype "passive"))
      (node (ref "S1") (pin "4") (pinfunction "2_4") (pintype "passive"))
      (node (ref "U3") (pin "~RST") (pinfunction "~{RST}_~RST") (pintype "bidirectional"))
    )
    (net (code "76") (name "~{RTS}") (class "Default")
      (node (ref "C13") (pin "1") (pinfunction "1_1") (pintype "passive"))
      (node (ref "C14") (pin "1") (pinfunction "1_1") (pintype "passive"))
      (node (ref "U4") (pin "4") (pinfunction "~{RTS}_4") (pintype "bidirectional"))
    )
  )
)
